# McPiFace-V1_1.net
KiCad netlist of a schematic drawn in EAGLE
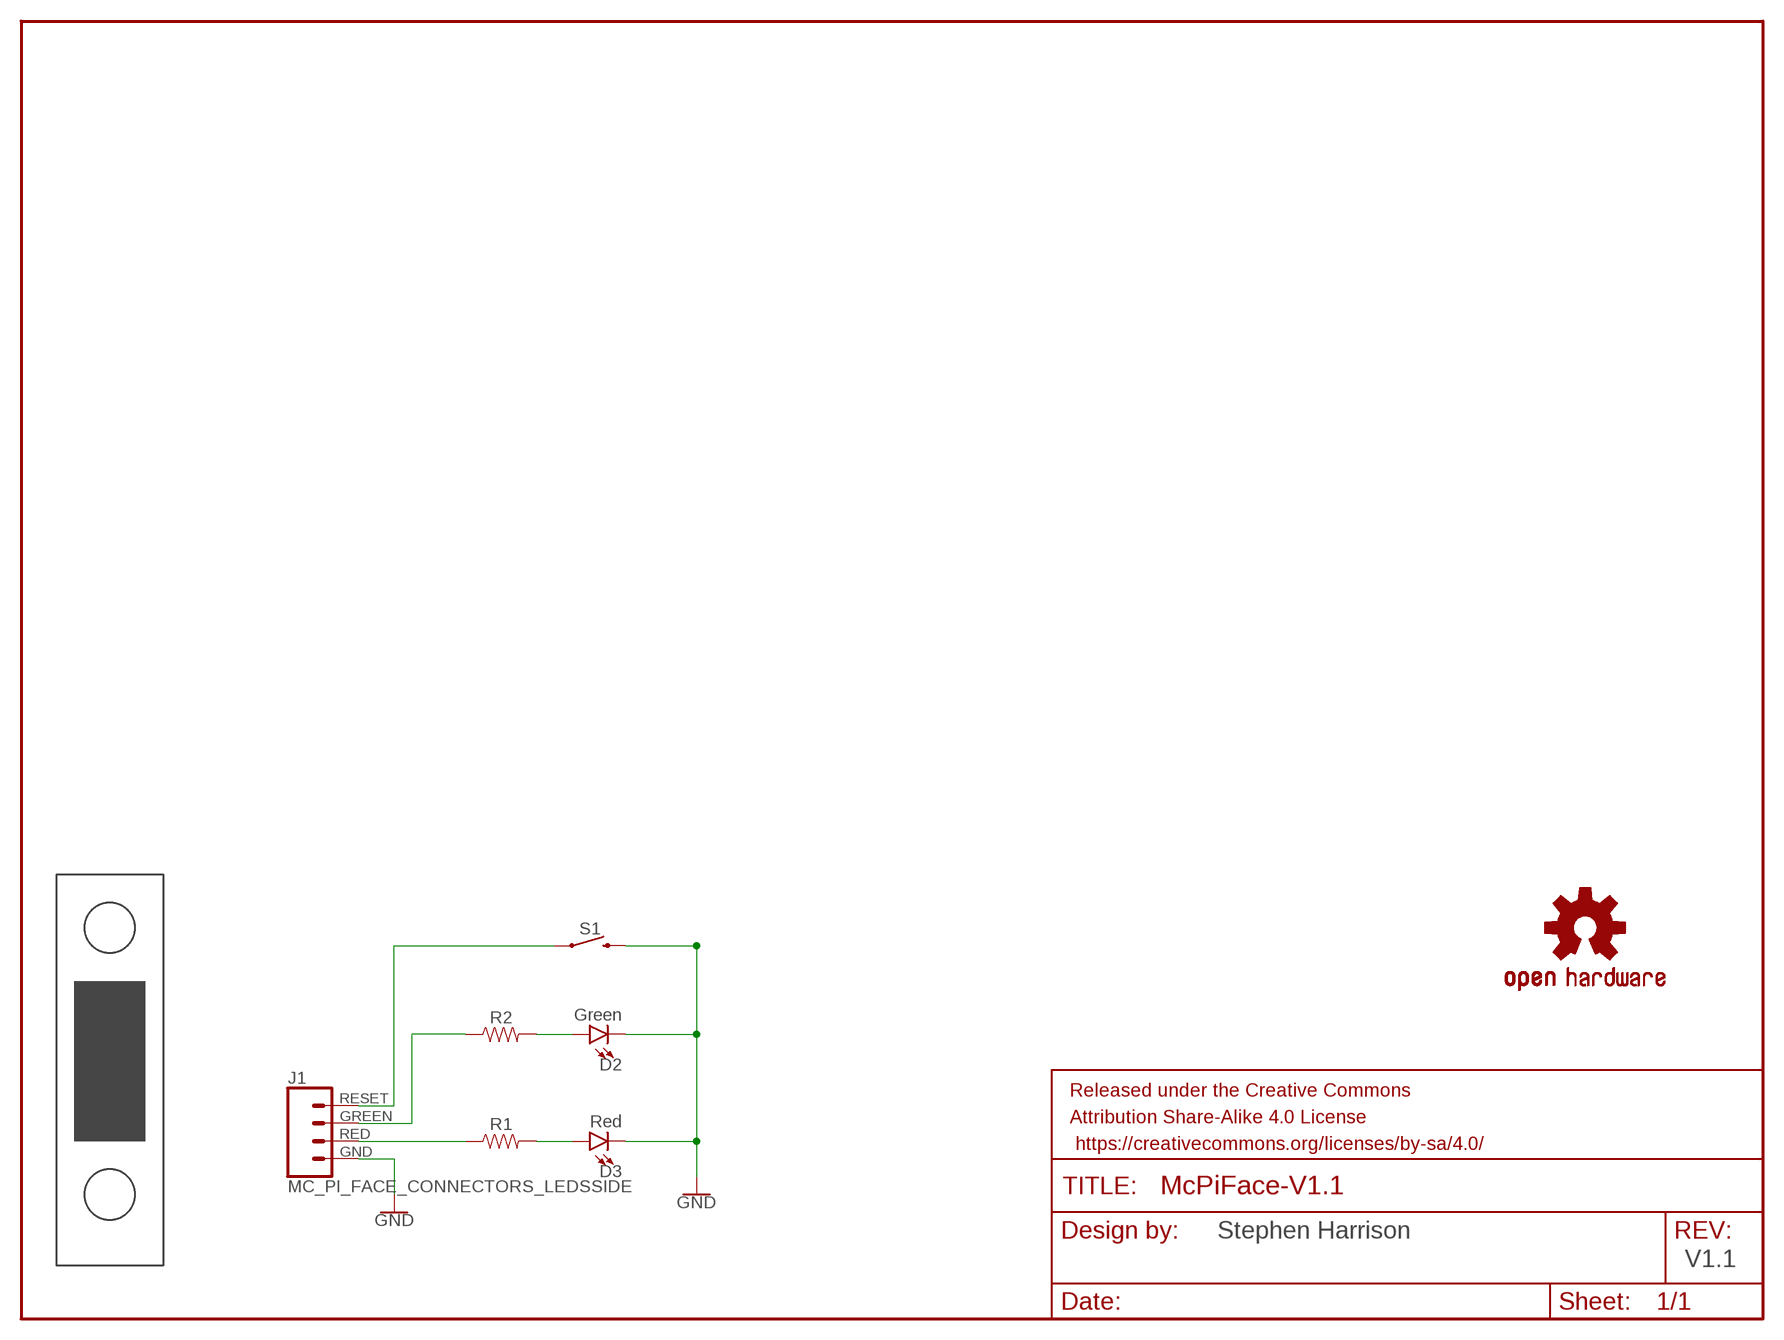
[diagram p0: schematic, sheet 1]

(export (version "E")
  (design (tool "Eeschema 10.0.6"))
  (components
    (comp (ref "D2")
      (value "Green")
      (footprint "eagle-import:LED-1206-BOTTOM-2.0MM")
      (libsource (lib "eagle-import") (part "LEDLED-1206-BOTTOM-2.0MM-GREEN"))
    )
    (comp (ref "D3")
      (value "Red")
      (footprint "eagle-import:LED-1206-BOTTOM-2.0MM")
      (libsource (lib "eagle-import") (part "LEDLED-1206-BOTTOM-2.0MM-RED"))
    )
    (comp (ref "FRAME1")
      (value "FRAME-LETTER")
      (footprint "eagle-import:CREATIVE_COMMONS")
      (libsource (lib "eagle-import") (part "FRAME-LETTER"))
    )
    (comp (ref "J1")
      (value "MC_PI_FACE_CONNECTORS_LEDSSIDE")
      (footprint "eagle-import:JST-4-SH-1.0MM-SIDE")
      (fields (field (name "MFG") "SM04B-SRSS-TB(LF)(SN)"))
      (libsource (lib "eagle-import") (part "MC_PI_FACE_CONNECTORS_LEDSSIDE"))
    )
    (comp (ref "LOGO1")
      (value "OSHW-LOGOL")
      (footprint "eagle-import:OSHW-LOGO-L")
      (libsource (lib "eagle-import") (part "OSHW-LOGOL"))
    )
    (comp (ref "R1")
      (value "RESISTOR0805")
      (footprint "eagle-import:0805")
      (libsource (lib "eagle-import") (part "RESISTOR0805"))
    )
    (comp (ref "R2")
      (value "RESISTOR0805")
      (footprint "eagle-import:0805")
      (libsource (lib "eagle-import") (part "RESISTOR0805"))
    )
    (comp (ref "S1")
      (value "MOMENTARY-SWITCH-SPSTTACKTILE_SWITCH_PTH_6.0MM_NO_TOP_RESIST")
      (footprint "eagle-import:TACTILE_SWITCH_PTH_6.0MM_NO_TOP_RESIST")
      (libsource (lib "eagle-import") (part "MOMENTARY-SWITCH-SPSTTACKTILE_SWITCH_PTH_6.0MM_NO_TOP_RESIST"))
    )
    (comp (ref "U$1")
      (value "MC_PI_FACE_PANELSINGLE")
      (footprint "eagle-import:MC_PI_FACE_JOINT")
      (libsource (lib "eagle-import") (part "MC_PI_FACE_PANELSINGLE"))
    )
  )
  (nets
    (net (code "1") (name "GND") (class "Default")
      (node (ref "D2") (pin "C") (pinfunction "C_C") (pintype "passive"))
      (node (ref "D3") (pin "C") (pinfunction "C_C") (pintype "passive"))
      (node (ref "J1") (pin "GND") (pinfunction "GND_GND") (pintype "power_in"))
      (node (ref "S1") (pin "3") (pinfunction "2_3") (pintype "passive"))
    )
    (net (code "2") (name "Net-(D2-PadA)") (class "Default")
      (node (ref "D2") (pin "A") (pinfunction "A_A") (pintype "passive"))
      (node (ref "R2") (pin "2") (pinfunction "2_2") (pintype "passive"))
    )
    (net (code "3") (name "Net-(D3-PadA)") (class "Default")
      (node (ref "D3") (pin "A") (pinfunction "A_A") (pintype "passive"))
      (node (ref "R1") (pin "2") (pinfunction "2_2") (pintype "passive"))
    )
    (net (code "4") (name "Net-(J1-PadGREEN)") (class "Default")
      (node (ref "J1") (pin "GREEN") (pinfunction "GREEN_GREEN") (pintype "passive"))
      (node (ref "R2") (pin "1") (pinfunction "1_1") (pintype "passive"))
    )
    (net (code "5") (name "Net-(J1-PadRED)") (class "Default")
      (node (ref "J1") (pin "RED") (pinfunction "RED_RED") (pintype "passive"))
      (node (ref "R1") (pin "1") (pinfunction "1_1") (pintype "passive"))
    )
    (net (code "6") (name "Net-(J1-PadRESET)") (class "Default")
      (node (ref "J1") (pin "RESET") (pinfunction "RESET_RESET") (pintype "passive"))
      (node (ref "S1") (pin "1") (pinfunction "1_1") (pintype "passive"))
    )
  )
)
